# tulip_breakout.net
KiCad netlist of a schematic drawn in EAGLE
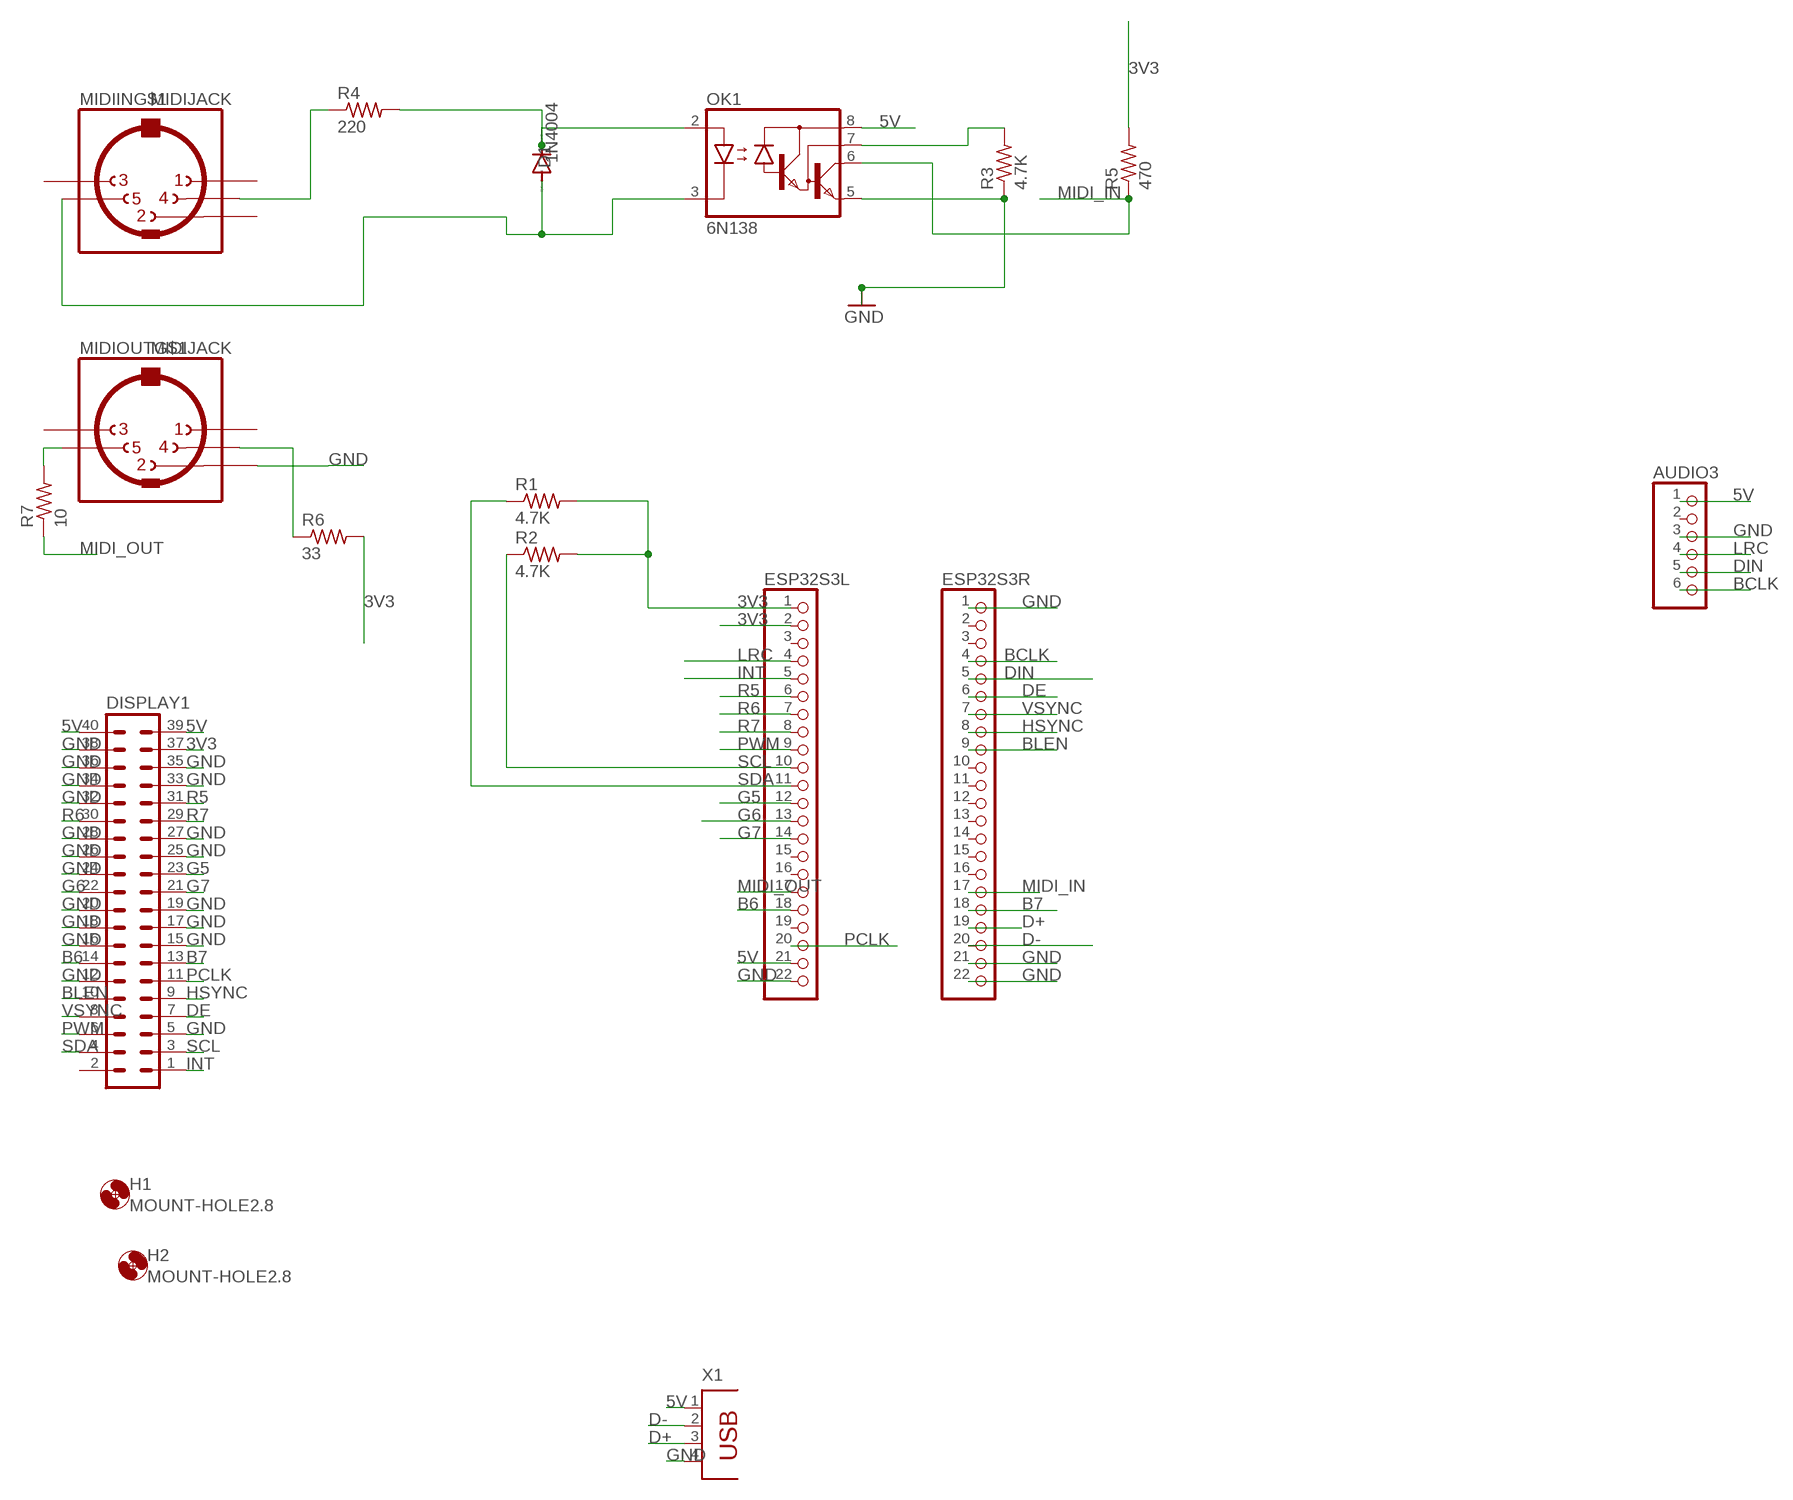
[diagram p0: schematic, sheet 1]

(export (version "E")
  (design (tool "Eeschema 10.0.6"))
  (components
    (comp (ref "AUDIO3")
      (value "PINHD-1X6")
      (footprint "eagle-import:1X06")
      (libsource (lib "eagle-import") (part "PINHD-1X6"))
    )
    (comp (ref "D1")
      (value "1N4004")
      (footprint "eagle-import:DO41-10")
      (libsource (lib "eagle-import") (part "1N4004"))
    )
    (comp (ref "DISPLAY1")
      (value "MA20-2")
      (footprint "eagle-import:MA20-2")
      (libsource (lib "eagle-import") (part "MA20-2"))
    )
    (comp (ref "ESP32S3L")
      (value "PINHD-1X22")
      (footprint "eagle-import:1X22")
      (libsource (lib "eagle-import") (part "PINHD-1X22"))
    )
    (comp (ref "ESP32S3R")
      (value "PINHD-1X22")
      (footprint "eagle-import:1X22")
      (libsource (lib "eagle-import") (part "PINHD-1X22"))
    )
    (comp (ref "H1")
      (value "MOUNT-HOLE2.8")
      (footprint "eagle-import:2,8")
      (libsource (lib "eagle-import") (part "MOUNT-HOLE2.8"))
    )
    (comp (ref "H2")
      (value "MOUNT-HOLE2.8")
      (footprint "eagle-import:2,8")
      (libsource (lib "eagle-import") (part "MOUNT-HOLE2.8"))
    )
    (comp (ref "MIDIIN")
      (value "MIDIJACK")
      (footprint "eagle-import:CP-2350")
      (libsource (lib "eagle-import") (part "MIDIJACK"))
    )
    (comp (ref "MIDIOUT")
      (value "MIDIJACK")
      (footprint "eagle-import:CP-2350")
      (libsource (lib "eagle-import") (part "MIDIJACK"))
    )
    (comp (ref "OK1")
      (value "6N138")
      (footprint "eagle-import:DIL08")
      (fields (field (name "MF") "VISHAY/TELEFUNKEN"))
      (libsource (lib "eagle-import") (part "6N138"))
    )
    (comp (ref "R1")
      (value "4.7K")
      (footprint "eagle-import:0207_12")
      (libsource (lib "eagle-import") (part "R-US_0207/12"))
    )
    (comp (ref "R2")
      (value "4.7K")
      (footprint "eagle-import:0207_12")
      (libsource (lib "eagle-import") (part "R-US_0207/12"))
    )
    (comp (ref "R3")
      (value "4.7K")
      (footprint "eagle-import:0207_12")
      (libsource (lib "eagle-import") (part "R-US_0207/12"))
    )
    (comp (ref "R4")
      (value "220")
      (footprint "eagle-import:0207_12")
      (libsource (lib "eagle-import") (part "R-US_0207/12"))
    )
    (comp (ref "R5")
      (value "470")
      (footprint "eagle-import:0207_12")
      (libsource (lib "eagle-import") (part "R-US_0207/12"))
    )
    (comp (ref "R6")
      (value "33")
      (footprint "eagle-import:0207_12")
      (libsource (lib "eagle-import") (part "R-US_0207/12"))
    )
    (comp (ref "R7")
      (value "10")
      (footprint "eagle-import:0207_12")
      (libsource (lib "eagle-import") (part "R-US_0207/12"))
    )
    (comp (ref "X1")
      (value "PN87520")
      (footprint "eagle-import:PN87520")
      (libsource (lib "eagle-import") (part "PN87520"))
    )
  )
  (nets
    (net (code "1") (name "/3V3") (class "Default")
      (node (ref "DISPLAY1") (pin "37") (pinfunction "37_37") (pintype "passive"))
      (node (ref "ESP32S3L") (pin "1") (pinfunction "1_1") (pintype "passive"))
      (node (ref "ESP32S3L") (pin "2") (pinfunction "2_2") (pintype "passive"))
      (node (ref "R1") (pin "2") (pinfunction "2_2") (pintype "passive"))
      (node (ref "R2") (pin "2") (pinfunction "2_2") (pintype "passive"))
      (node (ref "R5") (pin "2") (pinfunction "2_2") (pintype "passive"))
      (node (ref "R6") (pin "2") (pinfunction "2_2") (pintype "passive"))
    )
    (net (code "2") (name "/5V") (class "Default")
      (node (ref "AUDIO3") (pin "1") (pinfunction "1_1") (pintype "passive"))
      (node (ref "DISPLAY1") (pin "39") (pinfunction "39_39") (pintype "passive"))
      (node (ref "DISPLAY1") (pin "40") (pinfunction "40_40") (pintype "passive"))
      (node (ref "ESP32S3L") (pin "21") (pinfunction "21_21") (pintype "passive"))
      (node (ref "OK1") (pin "8") (pinfunction "VCC_8") (pintype "passive"))
      (node (ref "X1") (pin "1") (pinfunction "1_1") (pintype "passive"))
    )
    (net (code "3") (name "/B6") (class "Default")
      (node (ref "DISPLAY1") (pin "14") (pinfunction "14_14") (pintype "passive"))
      (node (ref "ESP32S3L") (pin "18") (pinfunction "18_18") (pintype "passive"))
    )
    (net (code "4") (name "/B7") (class "Default")
      (node (ref "DISPLAY1") (pin "13") (pinfunction "13_13") (pintype "passive"))
      (node (ref "ESP32S3R") (pin "18") (pinfunction "18_18") (pintype "passive"))
    )
    (net (code "5") (name "/BCLK") (class "Default")
      (node (ref "AUDIO3") (pin "6") (pinfunction "6_6") (pintype "passive"))
      (node (ref "ESP32S3R") (pin "4") (pinfunction "4_4") (pintype "passive"))
    )
    (net (code "6") (name "/BLEN") (class "Default")
      (node (ref "DISPLAY1") (pin "10") (pinfunction "10_10") (pintype "passive"))
      (node (ref "ESP32S3R") (pin "9") (pinfunction "9_9") (pintype "passive"))
    )
    (net (code "7") (name "/D+") (class "Default")
      (node (ref "ESP32S3R") (pin "19") (pinfunction "19_19") (pintype "passive"))
      (node (ref "X1") (pin "3") (pinfunction "3_3") (pintype "passive"))
    )
    (net (code "8") (name "/D-") (class "Default")
      (node (ref "ESP32S3R") (pin "20") (pinfunction "20_20") (pintype "passive"))
      (node (ref "X1") (pin "2") (pinfunction "2_2") (pintype "passive"))
    )
    (net (code "9") (name "/DE") (class "Default")
      (node (ref "DISPLAY1") (pin "7") (pinfunction "7_7") (pintype "passive"))
      (node (ref "ESP32S3R") (pin "6") (pinfunction "6_6") (pintype "passive"))
    )
    (net (code "10") (name "/DIN") (class "Default")
      (node (ref "AUDIO3") (pin "5") (pinfunction "5_5") (pintype "passive"))
      (node (ref "ESP32S3R") (pin "5") (pinfunction "5_5") (pintype "passive"))
    )
    (net (code "11") (name "/G5") (class "Default")
      (node (ref "DISPLAY1") (pin "23") (pinfunction "23_23") (pintype "passive"))
      (node (ref "ESP32S3L") (pin "12") (pinfunction "12_12") (pintype "passive"))
    )
    (net (code "12") (name "/G6") (class "Default")
      (node (ref "DISPLAY1") (pin "22") (pinfunction "22_22") (pintype "passive"))
      (node (ref "ESP32S3L") (pin "13") (pinfunction "13_13") (pintype "passive"))
    )
    (net (code "13") (name "/G7") (class "Default")
      (node (ref "DISPLAY1") (pin "21") (pinfunction "21_21") (pintype "passive"))
      (node (ref "ESP32S3L") (pin "14") (pinfunction "14_14") (pintype "passive"))
    )
    (net (code "14") (name "/HSYNC") (class "Default")
      (node (ref "DISPLAY1") (pin "9") (pinfunction "9_9") (pintype "passive"))
      (node (ref "ESP32S3R") (pin "8") (pinfunction "8_8") (pintype "passive"))
    )
    (net (code "15") (name "/INT") (class "Default")
      (node (ref "DISPLAY1") (pin "1") (pinfunction "1_1") (pintype "passive"))
      (node (ref "ESP32S3L") (pin "5") (pinfunction "5_5") (pintype "passive"))
    )
    (net (code "16") (name "/LRC") (class "Default")
      (node (ref "AUDIO3") (pin "4") (pinfunction "4_4") (pintype "passive"))
      (node (ref "ESP32S3L") (pin "4") (pinfunction "4_4") (pintype "passive"))
    )
    (net (code "17") (name "/MIDI_IN") (class "Default")
      (node (ref "ESP32S3R") (pin "17") (pinfunction "17_17") (pintype "passive"))
      (node (ref "OK1") (pin "6") (pinfunction "VO_6") (pintype "passive"))
      (node (ref "R5") (pin "1") (pinfunction "1_1") (pintype "passive"))
    )
    (net (code "18") (name "/MIDI_OUT") (class "Default")
      (node (ref "ESP32S3L") (pin "17") (pinfunction "17_17") (pintype "passive"))
      (node (ref "R7") (pin "1") (pinfunction "1_1") (pintype "passive"))
    )
    (net (code "19") (name "/PCLK") (class "Default")
      (node (ref "DISPLAY1") (pin "11") (pinfunction "11_11") (pintype "passive"))
      (node (ref "ESP32S3L") (pin "20") (pinfunction "20_20") (pintype "passive"))
    )
    (net (code "20") (name "/PWM") (class "Default")
      (node (ref "DISPLAY1") (pin "6") (pinfunction "6_6") (pintype "passive"))
      (node (ref "ESP32S3L") (pin "9") (pinfunction "9_9") (pintype "passive"))
    )
    (net (code "21") (name "/R5") (class "Default")
      (node (ref "DISPLAY1") (pin "31") (pinfunction "31_31") (pintype "passive"))
      (node (ref "ESP32S3L") (pin "6") (pinfunction "6_6") (pintype "passive"))
    )
    (net (code "22") (name "/R6") (class "Default")
      (node (ref "DISPLAY1") (pin "30") (pinfunction "30_30") (pintype "passive"))
      (node (ref "ESP32S3L") (pin "7") (pinfunction "7_7") (pintype "passive"))
    )
    (net (code "23") (name "/R7") (class "Default")
      (node (ref "DISPLAY1") (pin "29") (pinfunction "29_29") (pintype "passive"))
      (node (ref "ESP32S3L") (pin "8") (pinfunction "8_8") (pintype "passive"))
    )
    (net (code "24") (name "/SCL") (class "Default")
      (node (ref "DISPLAY1") (pin "3") (pinfunction "3_3") (pintype "passive"))
      (node (ref "ESP32S3L") (pin "10") (pinfunction "10_10") (pintype "passive"))
      (node (ref "R2") (pin "1") (pinfunction "1_1") (pintype "passive"))
    )
    (net (code "25") (name "/SDA") (class "Default")
      (node (ref "DISPLAY1") (pin "4") (pinfunction "4_4") (pintype "passive"))
      (node (ref "ESP32S3L") (pin "11") (pinfunction "11_11") (pintype "passive"))
      (node (ref "R1") (pin "1") (pinfunction "1_1") (pintype "passive"))
    )
    (net (code "26") (name "/VSYNC") (class "Default")
      (node (ref "DISPLAY1") (pin "8") (pinfunction "8_8") (pintype "passive"))
      (node (ref "ESP32S3R") (pin "7") (pinfunction "7_7") (pintype "passive"))
    )
    (net (code "27") (name "GND") (class "Default")
      (node (ref "AUDIO3") (pin "3") (pinfunction "3_3") (pintype "passive"))
      (node (ref "DISPLAY1") (pin "12") (pinfunction "12_12") (pintype "passive"))
      (node (ref "DISPLAY1") (pin "15") (pinfunction "15_15") (pintype "passive"))
      (node (ref "DISPLAY1") (pin "16") (pinfunction "16_16") (pintype "passive"))
      (node (ref "DISPLAY1") (pin "17") (pinfunction "17_17") (pintype "passive"))
      (node (ref "DISPLAY1") (pin "18") (pinfunction "18_18") (pintype "passive"))
      (node (ref "DISPLAY1") (pin "19") (pinfunction "19_19") (pintype "passive"))
      (node (ref "DISPLAY1") (pin "20") (pinfunction "20_20") (pintype "passive"))
      (node (ref "DISPLAY1") (pin "24") (pinfunction "24_24") (pintype "passive"))
      (node (ref "DISPLAY1") (pin "25") (pinfunction "25_25") (pintype "passive"))
      (node (ref "DISPLAY1") (pin "26") (pinfunction "26_26") (pintype "passive"))
      (node (ref "DISPLAY1") (pin "27") (pinfunction "27_27") (pintype "passive"))
      (node (ref "DISPLAY1") (pin "28") (pinfunction "28_28") (pintype "passive"))
      (node (ref "DISPLAY1") (pin "32") (pinfunction "32_32") (pintype "passive"))
      (node (ref "DISPLAY1") (pin "33") (pinfunction "33_33") (pintype "passive"))
      (node (ref "DISPLAY1") (pin "34") (pinfunction "34_34") (pintype "passive"))
      (node (ref "DISPLAY1") (pin "35") (pinfunction "35_35") (pintype "passive"))
      (node (ref "DISPLAY1") (pin "36") (pinfunction "36_36") (pintype "passive"))
      (node (ref "DISPLAY1") (pin "38") (pinfunction "38_38") (pintype "passive"))
      (node (ref "DISPLAY1") (pin "5") (pinfunction "5_5") (pintype "passive"))
      (node (ref "ESP32S3L") (pin "22") (pinfunction "22_22") (pintype "passive"))
      (node (ref "ESP32S3R") (pin "1") (pinfunction "1_1") (pintype "passive"))
      (node (ref "ESP32S3R") (pin "21") (pinfunction "21_21") (pintype "passive"))
      (node (ref "ESP32S3R") (pin "22") (pinfunction "22_22") (pintype "passive"))
      (node (ref "MIDIOUT") (pin "2") (pinfunction "2_2") (pintype "passive"))
      (node (ref "OK1") (pin "5") (pinfunction "GND_5") (pintype "passive"))
      (node (ref "R3") (pin "1") (pinfunction "1_1") (pintype "passive"))
      (node (ref "X1") (pin "4") (pinfunction "4_4") (pintype "passive"))
    )
    (net (code "28") (name "Net-(MIDIIN-Pad4)") (class "Default")
      (node (ref "MIDIIN") (pin "4") (pinfunction "4_4") (pintype "passive"))
      (node (ref "R4") (pin "1") (pinfunction "1_1") (pintype "passive"))
    )
    (net (code "29") (name "Net-(MIDIOUT-Pad4)") (class "Default")
      (node (ref "MIDIOUT") (pin "4") (pinfunction "4_4") (pintype "passive"))
      (node (ref "R6") (pin "1") (pinfunction "1_1") (pintype "passive"))
    )
    (net (code "30") (name "Net-(MIDIOUT-Pad5)") (class "Default")
      (node (ref "MIDIOUT") (pin "5") (pinfunction "5_5") (pintype "passive"))
      (node (ref "R7") (pin "2") (pinfunction "2_2") (pintype "passive"))
    )
    (net (code "31") (name "Net-(OK1-A)") (class "Default")
      (node (ref "D1") (pin "C") (pinfunction "C_C") (pintype "passive"))
      (node (ref "OK1") (pin "2") (pinfunction "A_2") (pintype "passive"))
      (node (ref "R4") (pin "2") (pinfunction "2_2") (pintype "passive"))
    )
    (net (code "32") (name "Net-(OK1-C)") (class "Default")
      (node (ref "D1") (pin "A") (pinfunction "A_A") (pintype "passive"))
      (node (ref "MIDIIN") (pin "5") (pinfunction "5_5") (pintype "passive"))
      (node (ref "OK1") (pin "3") (pinfunction "C_3") (pintype "passive"))
    )
    (net (code "33") (name "Net-(OK1-VB)") (class "Default")
      (node (ref "OK1") (pin "7") (pinfunction "VB_7") (pintype "passive"))
      (node (ref "R3") (pin "2") (pinfunction "2_2") (pintype "passive"))
    )
    (net (code "34") (name "unconnected-(AUDIO3-Pad2)") (class "Default")
      (node (ref "AUDIO3") (pin "2") (pinfunction "2_2") (pintype "passive"))
    )
    (net (code "35") (name "unconnected-(DISPLAY1-Pad2)") (class "Default")
      (node (ref "DISPLAY1") (pin "2") (pinfunction "2_2") (pintype "passive"))
    )
    (net (code "36") (name "unconnected-(ESP32S3L-Pad3)") (class "Default")
      (node (ref "ESP32S3L") (pin "3") (pinfunction "3_3") (pintype "passive"))
    )
    (net (code "37") (name "unconnected-(ESP32S3L-Pad15)") (class "Default")
      (node (ref "ESP32S3L") (pin "15") (pinfunction "15_15") (pintype "passive"))
    )
    (net (code "38") (name "unconnected-(ESP32S3L-Pad16)") (class "Default")
      (node (ref "ESP32S3L") (pin "16") (pinfunction "16_16") (pintype "passive"))
    )
    (net (code "39") (name "unconnected-(ESP32S3L-Pad19)") (class "Default")
      (node (ref "ESP32S3L") (pin "19") (pinfunction "19_19") (pintype "passive"))
    )
    (net (code "40") (name "unconnected-(ESP32S3R-Pad2)") (class "Default")
      (node (ref "ESP32S3R") (pin "2") (pinfunction "2_2") (pintype "passive"))
    )
    (net (code "41") (name "unconnected-(ESP32S3R-Pad3)") (class "Default")
      (node (ref "ESP32S3R") (pin "3") (pinfunction "3_3") (pintype "passive"))
    )
    (net (code "42") (name "unconnected-(ESP32S3R-Pad10)") (class "Default")
      (node (ref "ESP32S3R") (pin "10") (pinfunction "10_10") (pintype "passive"))
    )
    (net (code "43") (name "unconnected-(ESP32S3R-Pad11)") (class "Default")
      (node (ref "ESP32S3R") (pin "11") (pinfunction "11_11") (pintype "passive"))
    )
    (net (code "44") (name "unconnected-(ESP32S3R-Pad12)") (class "Default")
      (node (ref "ESP32S3R") (pin "12") (pinfunction "12_12") (pintype "passive"))
    )
    (net (code "45") (name "unconnected-(ESP32S3R-Pad13)") (class "Default")
      (node (ref "ESP32S3R") (pin "13") (pinfunction "13_13") (pintype "passive"))
    )
    (net (code "46") (name "unconnected-(ESP32S3R-Pad14)") (class "Default")
      (node (ref "ESP32S3R") (pin "14") (pinfunction "14_14") (pintype "passive"))
    )
    (net (code "47") (name "unconnected-(ESP32S3R-Pad15)") (class "Default")
      (node (ref "ESP32S3R") (pin "15") (pinfunction "15_15") (pintype "passive"))
    )
    (net (code "48") (name "unconnected-(ESP32S3R-Pad16)") (class "Default")
      (node (ref "ESP32S3R") (pin "16") (pinfunction "16_16") (pintype "passive"))
    )
    (net (code "49") (name "unconnected-(MIDIIN-Pad1)") (class "Default")
      (node (ref "MIDIIN") (pin "1") (pinfunction "1_1") (pintype "passive"))
    )
    (net (code "50") (name "unconnected-(MIDIIN-Pad2)") (class "Default")
      (node (ref "MIDIIN") (pin "2") (pinfunction "2_2") (pintype "passive"))
    )
    (net (code "51") (name "unconnected-(MIDIIN-Pad3)") (class "Default")
      (node (ref "MIDIIN") (pin "3") (pinfunction "3_3") (pintype "passive"))
    )
    (net (code "52") (name "unconnected-(MIDIOUT-Pad1)") (class "Default")
      (node (ref "MIDIOUT") (pin "1") (pinfunction "1_1") (pintype "passive"))
    )
    (net (code "53") (name "unconnected-(MIDIOUT-Pad3)") (class "Default")
      (node (ref "MIDIOUT") (pin "3") (pinfunction "3_3") (pintype "passive"))
    )
  )
)
